# SoC_FPGA_67_68_69_DDR4.net
KiCad netlist of a schematic drawn in Altium Designer
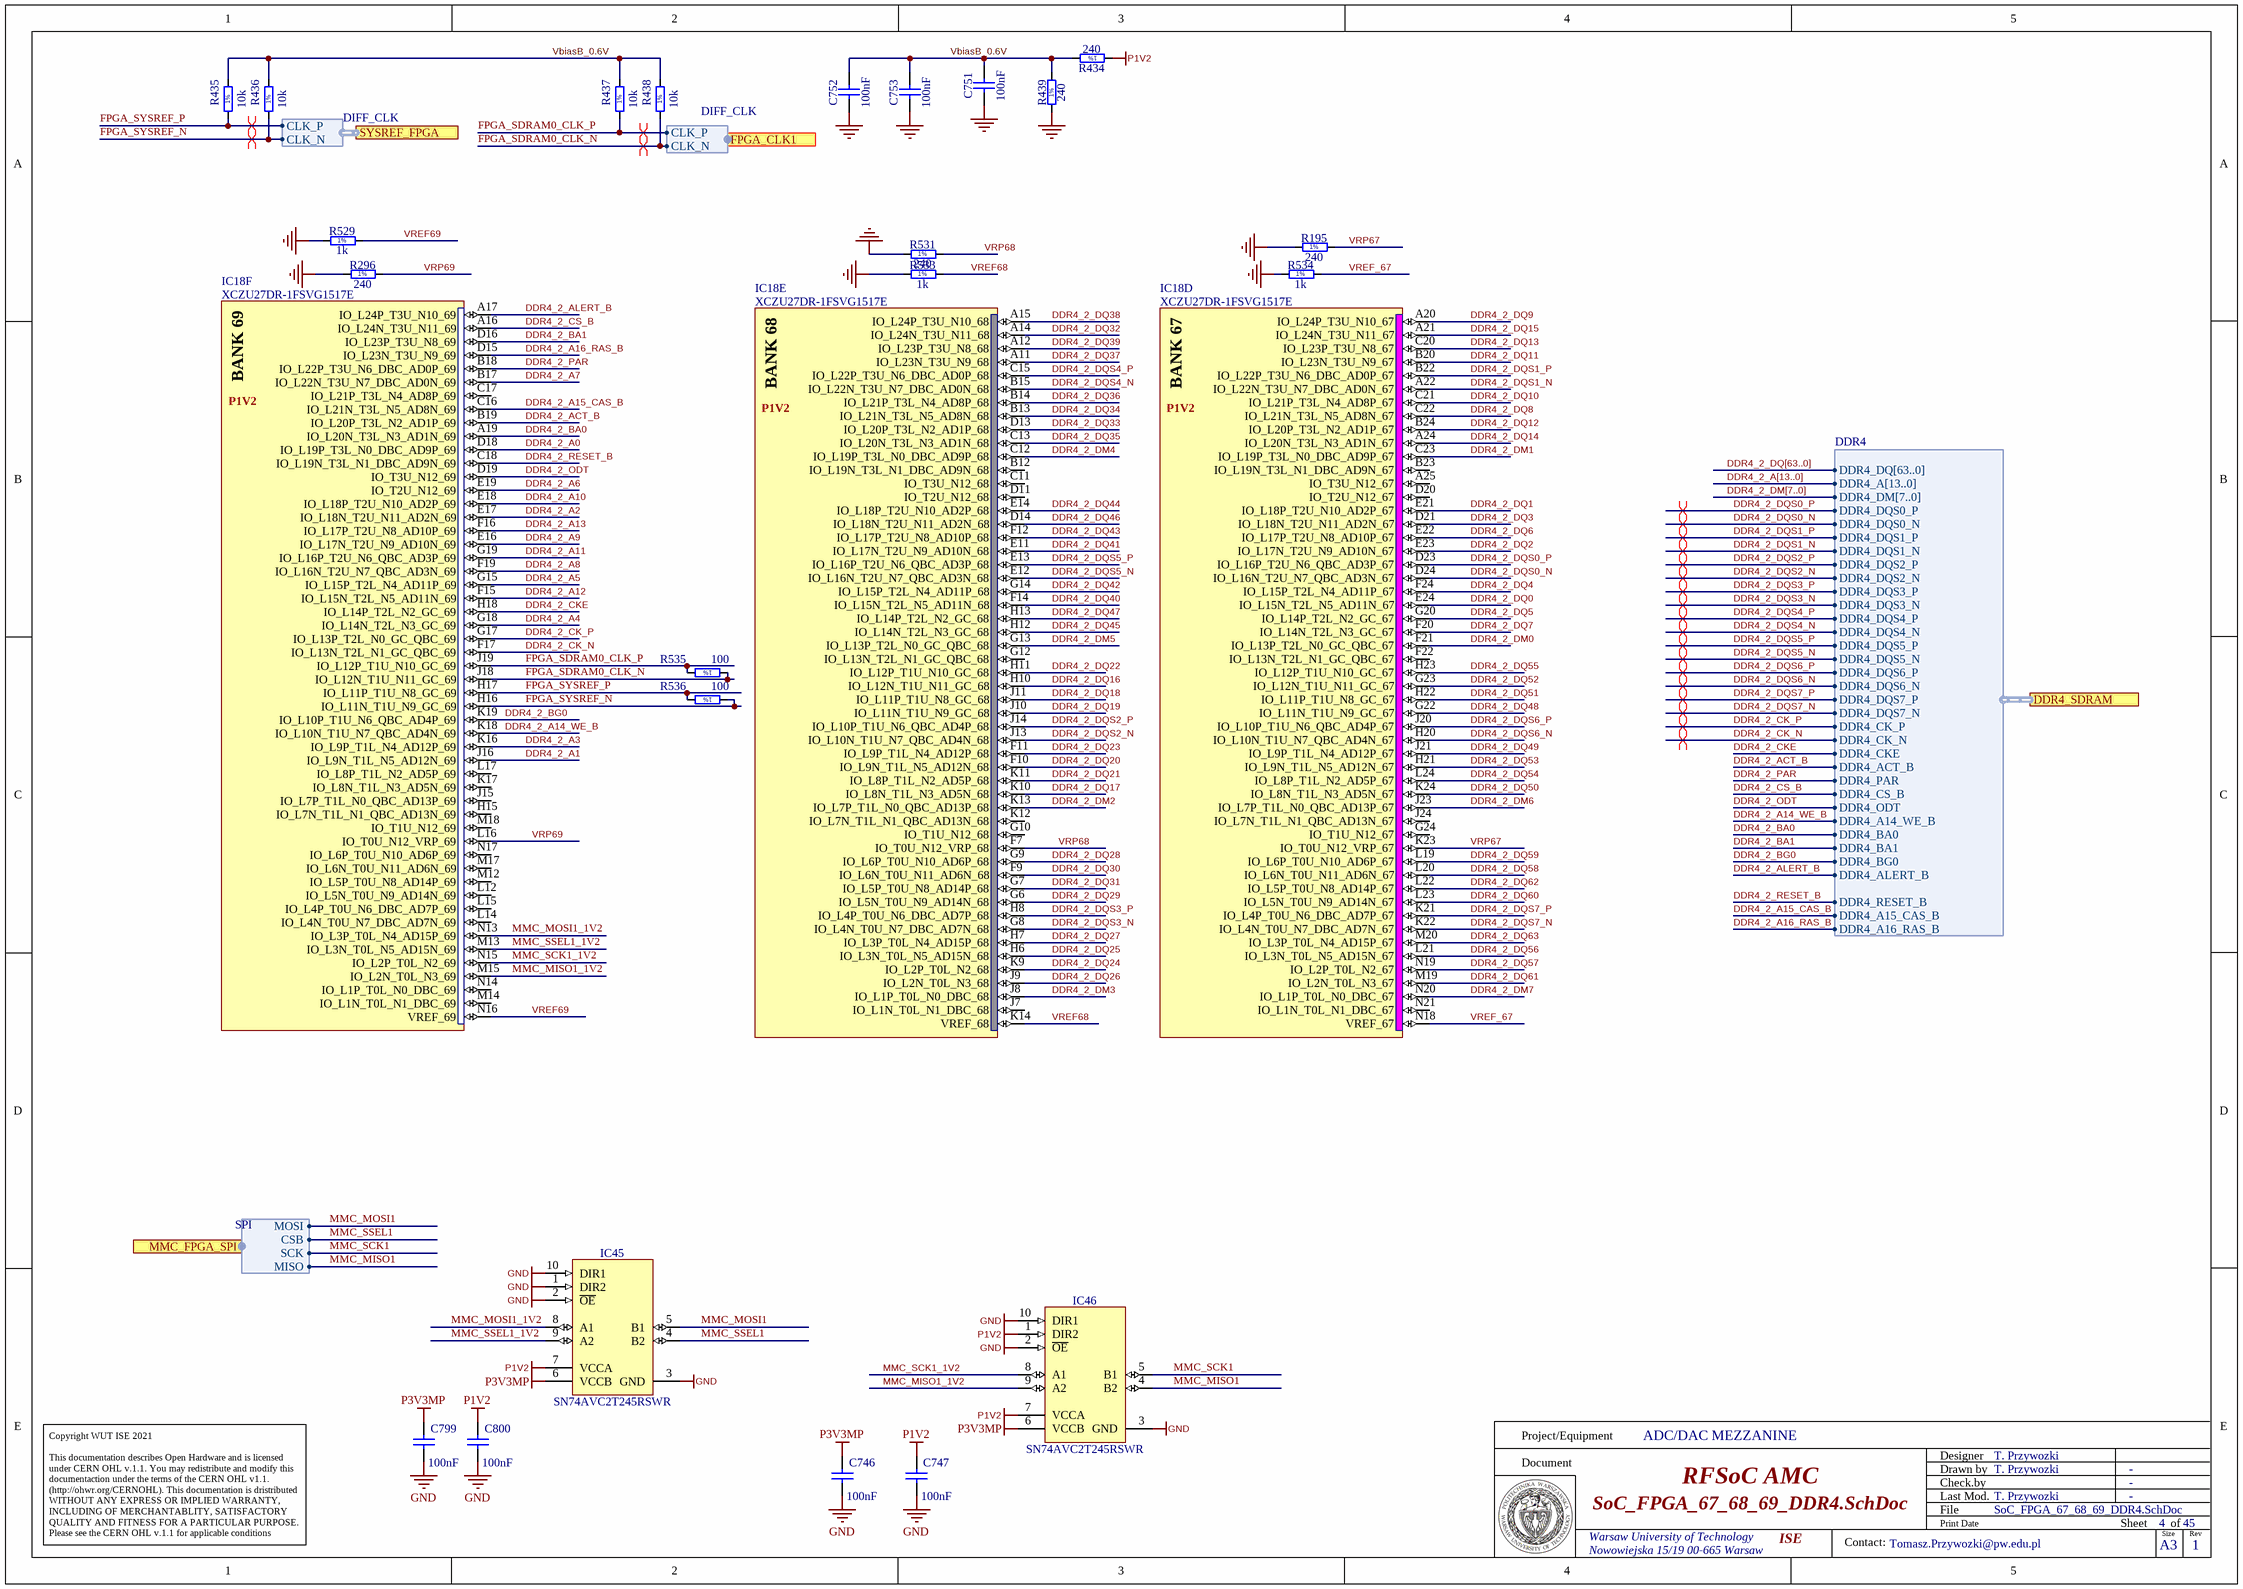
[diagram p0: SoC_FPGA_67_68_69_DDR4.SchDoc]

(export (version "E")
  (design (tool "Eeschema 10.0.6"))
  (components
    (comp (ref "C746")
      (value "100nF")
      (footprint "CAPC0603X33N")
      (description "Non-polarised capacitor")
      (fields
        (field (name "MANUFACTURER PART NUMBER") "CC0201_100NF_6.3V_10%_X5R")
        (field (name "MANUFACTURER") "GENERIC")
        (field (name "AUTHOR") "CERN DEM JLC")
      )
      (libsource (lib "Capacitors") (part "Capacitor - non polarized"))
    )
    (comp (ref "C747")
      (value "100nF")
      (footprint "CAPC0603X33N")
      (description "Non-polarised capacitor")
      (fields
        (field (name "MANUFACTURER PART NUMBER") "CC0201_100NF_6.3V_10%_X5R")
        (field (name "MANUFACTURER") "GENERIC")
        (field (name "AUTHOR") "CERN DEM JLC")
      )
      (libsource (lib "Capacitors") (part "Capacitor - non polarized"))
    )
    (comp (ref "C751")
      (value "100nF")
      (footprint "CAPC0603X33N")
      (description "Non-polarised capacitor")
      (fields
        (field (name "MANUFACTURER PART NUMBER") "CC0201_100NF_6.3V_10%_X5R")
        (field (name "MANUFACTURER") "GENERIC")
        (field (name "AUTHOR") "CERN DEM JLC")
      )
      (libsource (lib "Capacitors") (part "Capacitor - non polarized"))
    )
    (comp (ref "C752")
      (value "100nF")
      (footprint "CAPC0603X33N")
      (description "Non-polarised capacitor")
      (fields
        (field (name "MANUFACTURER PART NUMBER") "CC0201_100NF_6.3V_10%_X5R")
        (field (name "MANUFACTURER") "GENERIC")
        (field (name "AUTHOR") "CERN DEM JLC")
      )
      (libsource (lib "Capacitors") (part "Capacitor - non polarized"))
    )
    (comp (ref "C753")
      (value "100nF")
      (footprint "CAPC0603X33N")
      (description "Non-polarised capacitor")
      (fields
        (field (name "MANUFACTURER PART NUMBER") "CC0201_100NF_6.3V_10%_X5R")
        (field (name "MANUFACTURER") "GENERIC")
        (field (name "AUTHOR") "CERN DEM JLC")
      )
      (libsource (lib "Capacitors") (part "Capacitor - non polarized"))
    )
    (comp (ref "C799")
      (value "100nF")
      (footprint "CAPC0603X33N")
      (description "Non-polarised capacitor")
      (fields
        (field (name "MANUFACTURER PART NUMBER") "CC0201_100NF_6.3V_10%_X5R")
        (field (name "MANUFACTURER") "GENERIC")
        (field (name "AUTHOR") "CERN DEM JLC")
      )
      (libsource (lib "Capacitors") (part "Capacitor - non polarized"))
    )
    (comp (ref "C800")
      (value "100nF")
      (footprint "CAPC0603X33N")
      (description "Non-polarised capacitor")
      (fields
        (field (name "MANUFACTURER PART NUMBER") "CC0201_100NF_6.3V_10%_X5R")
        (field (name "MANUFACTURER") "GENERIC")
        (field (name "AUTHOR") "CERN DEM JLC")
      )
      (libsource (lib "Capacitors") (part "Capacitor - non polarized"))
    )
    (comp (ref "IC18")
      (value "XCZU27DR-1FSVG1517E")
      (footprint "XILINX_FSVG1517 (XCZU27DR)")
      (fields (field (name "MANUFACTURER") "XILINX") (field (name "AUTHOR") "CERN DEM MR"))
      (libsource (lib "ICs And Semiconductors") (part "XCZU27DR-1FSVG1517E"))
    )
    (comp (ref "IC45")
      (value "SN74AVC2T245RSWR")
      (footprint "QFN40P140X180X55-10N")
      (description "Dual-Bit Dual-Supply Bus Transceiver With Configurable Voltage Translation and 3-State Outputs")
      (fields (field (name "MANUFACTURER") "TEXAS INSTRUMENTS") (field (name "AUTHOR") "CERN DEM JLC"))
      (libsource (lib "ICs And Semiconductors") (part "742T245"))
    )
    (comp (ref "IC46")
      (value "SN74AVC2T245RSWR")
      (footprint "QFN40P140X180X55-10N")
      (description "Dual-Bit Dual-Supply Bus Transceiver With Configurable Voltage Translation and 3-State Outputs")
      (fields (field (name "MANUFACTURER") "TEXAS INSTRUMENTS") (field (name "AUTHOR") "CERN DEM JLC"))
      (libsource (lib "ICs And Semiconductors") (part "742T245"))
    )
    (comp (ref "R195")
      (value "240")
      (footprint "RESC1005X40N")
      (description "Resistor - 1%")
      (fields
        (field (name "MANUFACTURER PART NUMBER") "R0402_240R_1%_0.0625W_100PPM")
        (field (name "MANUFACTURER") "GENERIC")
        (field (name "AUTHOR") "CERN DEM JLC")
      )
      (libsource (lib "Resistors") (part "Resistor - 1%"))
    )
    (comp (ref "R296")
      (value "240")
      (footprint "RESC1005X40N")
      (description "Resistor - 1%")
      (fields
        (field (name "MANUFACTURER PART NUMBER") "R0402_240R_1%_0.0625W_100PPM")
        (field (name "MANUFACTURER") "GENERIC")
        (field (name "AUTHOR") "CERN DEM JLC")
      )
      (libsource (lib "Resistors") (part "Resistor - 1%"))
    )
    (comp (ref "R434")
      (value "240")
      (footprint "RESC1005X40N")
      (description "Resistor - 1%")
      (fields
        (field (name "MANUFACTURER PART NUMBER") "R0402_240R_1%_0.0625W_100PPM")
        (field (name "MANUFACTURER") "GENERIC")
        (field (name "AUTHOR") "CERN DEM JLC")
      )
      (libsource (lib "Resistors") (part "Resistor - 1%"))
    )
    (comp (ref "R435")
      (value "10k")
      (footprint "RESC1005X40N")
      (description "Resistor - 1%")
      (fields
        (field (name "MANUFACTURER PART NUMBER") "R0402_10K_1%_0.0625W_100PPM")
        (field (name "MANUFACTURER") "GENERIC")
        (field (name "AUTHOR") "CERN DEM JLC")
      )
      (libsource (lib "Resistors") (part "Resistor - 1%"))
    )
    (comp (ref "R436")
      (value "10k")
      (footprint "RESC1005X40N")
      (description "Resistor - 1%")
      (fields
        (field (name "MANUFACTURER PART NUMBER") "R0402_10K_1%_0.0625W_100PPM")
        (field (name "MANUFACTURER") "GENERIC")
        (field (name "AUTHOR") "CERN DEM JLC")
      )
      (libsource (lib "Resistors") (part "Resistor - 1%"))
    )
    (comp (ref "R437")
      (value "10k")
      (footprint "RESC1005X40N")
      (description "Resistor - 1%")
      (fields
        (field (name "MANUFACTURER PART NUMBER") "R0402_10K_1%_0.0625W_100PPM")
        (field (name "MANUFACTURER") "GENERIC")
        (field (name "AUTHOR") "CERN DEM JLC")
      )
      (libsource (lib "Resistors") (part "Resistor - 1%"))
    )
    (comp (ref "R438")
      (value "10k")
      (footprint "RESC1005X40N")
      (description "Resistor - 1%")
      (fields
        (field (name "MANUFACTURER PART NUMBER") "R0402_10K_1%_0.0625W_100PPM")
        (field (name "MANUFACTURER") "GENERIC")
        (field (name "AUTHOR") "CERN DEM JLC")
      )
      (libsource (lib "Resistors") (part "Resistor - 1%"))
    )
    (comp (ref "R439")
      (value "240")
      (footprint "RESC1005X40N")
      (description "Resistor - 1%")
      (fields
        (field (name "MANUFACTURER PART NUMBER") "R0402_240R_1%_0.0625W_100PPM")
        (field (name "MANUFACTURER") "GENERIC")
        (field (name "AUTHOR") "CERN DEM JLC")
      )
      (libsource (lib "Resistors") (part "Resistor - 1%"))
    )
    (comp (ref "R529")
      (value "1k")
      (footprint "RESC1005X40N")
      (description "Resistor - 1%")
      (fields
        (field (name "MANUFACTURER PART NUMBER") "R0402_1K_1%_0.0625W_100PPM")
        (field (name "MANUFACTURER") "GENERIC")
        (field (name "AUTHOR") "CERN DEM JLC")
      )
      (libsource (lib "Resistors") (part "Resistor - 1%"))
    )
    (comp (ref "R531")
      (value "240")
      (footprint "RESC1005X40N")
      (description "Resistor - 1%")
      (fields
        (field (name "MANUFACTURER PART NUMBER") "R0402_240R_1%_0.0625W_100PPM")
        (field (name "MANUFACTURER") "GENERIC")
        (field (name "AUTHOR") "CERN DEM JLC")
      )
      (libsource (lib "Resistors") (part "Resistor - 1%"))
    )
    (comp (ref "R533")
      (value "1k")
      (footprint "RESC1005X40N")
      (description "Resistor - 1%")
      (fields
        (field (name "MANUFACTURER PART NUMBER") "R0402_1K_1%_0.0625W_100PPM")
        (field (name "MANUFACTURER") "GENERIC")
        (field (name "AUTHOR") "CERN DEM JLC")
      )
      (libsource (lib "Resistors") (part "Resistor - 1%"))
    )
    (comp (ref "R534")
      (value "1k")
      (footprint "RESC1005X40N")
      (description "Resistor - 1%")
      (fields
        (field (name "MANUFACTURER PART NUMBER") "R0402_1K_1%_0.0625W_100PPM")
        (field (name "MANUFACTURER") "GENERIC")
        (field (name "AUTHOR") "CERN DEM JLC")
      )
      (libsource (lib "Resistors") (part "Resistor - 1%"))
    )
    (comp (ref "R535")
      (value "100")
      (footprint "RESC1005X40N")
      (description "Resistor - 1%")
      (fields
        (field (name "MANUFACTURER PART NUMBER") "R0402_100R_1%_0.0625W_100PPM")
        (field (name "MANUFACTURER") "GENERIC")
        (field (name "AUTHOR") "CERN DEM JLC")
      )
      (libsource (lib "Resistors") (part "Resistor - 1%"))
    )
    (comp (ref "R536")
      (value "100")
      (footprint "RESC1005X40N")
      (description "Resistor - 1%")
      (fields
        (field (name "MANUFACTURER PART NUMBER") "R0402_100R_1%_0.0625W_100PPM")
        (field (name "MANUFACTURER") "GENERIC")
        (field (name "AUTHOR") "CERN DEM JLC")
      )
      (libsource (lib "Resistors") (part "Resistor - 1%"))
    )
  )
  (nets
    (net (code "4") (name "/DDR4_2_A0") (class "Default")
      (node (ref "IC18") (pin "D18") (pinfunction "IO_L19P_T3L_N0_DBC_AD9P_69_D18") (pintype "bidirectional"))
    )
    (net (code "5") (name "/DDR4_2_A1") (class "Default")
      (node (ref "IC18") (pin "J16") (pinfunction "IO_L9N_T1L_N5_AD12N_69_J16") (pintype "bidirectional"))
    )
    (net (code "6") (name "/DDR4_2_A2") (class "Default")
      (node (ref "IC18") (pin "E17") (pinfunction "IO_L18N_T2U_N11_AD2N_69_E17") (pintype "bidirectional"))
    )
    (net (code "7") (name "/DDR4_2_A3") (class "Default")
      (node (ref "IC18") (pin "K16") (pinfunction "IO_L9P_T1L_N4_AD12P_69_K16") (pintype "bidirectional"))
    )
    (net (code "8") (name "/DDR4_2_A4") (class "Default")
      (node (ref "IC18") (pin "G18") (pinfunction "IO_L14N_T2L_N3_GC_69_G18") (pintype "bidirectional"))
    )
    (net (code "9") (name "/DDR4_2_A5") (class "Default")
      (node (ref "IC18") (pin "G15") (pinfunction "IO_L15P_T2L_N4_AD11P_69_G15") (pintype "bidirectional"))
    )
    (net (code "10") (name "/DDR4_2_A6") (class "Default")
      (node (ref "IC18") (pin "E19") (pinfunction "IO_T2U_N12_69_E19") (pintype "bidirectional"))
    )
    (net (code "11") (name "/DDR4_2_A7") (class "Default")
      (node (ref "IC18") (pin "B17") (pinfunction "IO_L22N_T3U_N7_DBC_AD0N_69_B17") (pintype "bidirectional"))
    )
    (net (code "12") (name "/DDR4_2_A8") (class "Default")
      (node (ref "IC18") (pin "F19") (pinfunction "IO_L16N_T2U_N7_QBC_AD3N_69_F19") (pintype "bidirectional"))
    )
    (net (code "13") (name "/DDR4_2_A9") (class "Default")
      (node (ref "IC18") (pin "E16") (pinfunction "IO_L17N_T2U_N9_AD10N_69_E16") (pintype "bidirectional"))
    )
    (net (code "14") (name "/DDR4_2_A10") (class "Default")
      (node (ref "IC18") (pin "E18") (pinfunction "IO_L18P_T2U_N10_AD2P_69_E18") (pintype "bidirectional"))
    )
    (net (code "15") (name "/DDR4_2_A11") (class "Default")
      (node (ref "IC18") (pin "G19") (pinfunction "IO_L16P_T2U_N6_QBC_AD3P_69_G19") (pintype "bidirectional"))
    )
    (net (code "16") (name "/DDR4_2_A12") (class "Default")
      (node (ref "IC18") (pin "F15") (pinfunction "IO_L15N_T2L_N5_AD11N_69_F15") (pintype "bidirectional"))
    )
    (net (code "17") (name "/DDR4_2_A13") (class "Default")
      (node (ref "IC18") (pin "F16") (pinfunction "IO_L17P_T2U_N8_AD10P_69_F16") (pintype "bidirectional"))
    )
    (net (code "18") (name "/DDR4_2_A14_WE_B") (class "Default")
      (node (ref "IC18") (pin "K18") (pinfunction "IO_L10N_T1U_N7_QBC_AD4N_69_K18") (pintype "bidirectional"))
    )
    (net (code "19") (name "/DDR4_2_A15_CAS_B") (class "Default")
      (node (ref "IC18") (pin "C16") (pinfunction "IO_L21N_T3L_N5_AD8N_69_C16") (pintype "bidirectional"))
    )
    (net (code "20") (name "/DDR4_2_A16_RAS_B") (class "Default")
      (node (ref "IC18") (pin "D15") (pinfunction "IO_L23N_T3U_N9_69_D15") (pintype "bidirectional"))
    )
    (net (code "21") (name "/DDR4_2_ACT_B") (class "Default")
      (node (ref "IC18") (pin "B19") (pinfunction "IO_L20P_T3L_N2_AD1P_69_B19") (pintype "bidirectional"))
    )
    (net (code "22") (name "/DDR4_2_ALERT_B") (class "Default")
      (node (ref "IC18") (pin "A17") (pinfunction "IO_L24P_T3U_N10_69_A17") (pintype "bidirectional"))
    )
    (net (code "24") (name "/DDR4_2_BA0") (class "Default")
      (node (ref "IC18") (pin "A19") (pinfunction "IO_L20N_T3L_N3_AD1N_69_A19") (pintype "bidirectional"))
    )
    (net (code "25") (name "/DDR4_2_BA1") (class "Default")
      (node (ref "IC18") (pin "D16") (pinfunction "IO_L23P_T3U_N8_69_D16") (pintype "bidirectional"))
    )
    (net (code "26") (name "/DDR4_2_BG0") (class "Default")
      (node (ref "IC18") (pin "K19") (pinfunction "IO_L10P_T1U_N6_QBC_AD4P_69_K19") (pintype "bidirectional"))
    )
    (net (code "27") (name "/DDR4_2_CKE") (class "Default")
      (node (ref "IC18") (pin "H18") (pinfunction "IO_L14P_T2L_N2_GC_69_H18") (pintype "bidirectional"))
    )
    (net (code "28") (name "/DDR4_2_CK_N") (class "Default")
      (node (ref "IC18") (pin "F17") (pinfunction "IO_L13N_T2L_N1_GC_QBC_69_F17") (pintype "bidirectional"))
    )
    (net (code "29") (name "/DDR4_2_CK_P") (class "Default")
      (node (ref "IC18") (pin "G17") (pinfunction "IO_L13P_T2L_N0_GC_QBC_69_G17") (pintype "bidirectional"))
    )
    (net (code "30") (name "/DDR4_2_CS_B") (class "Default")
      (node (ref "IC18") (pin "A16") (pinfunction "IO_L24N_T3U_N11_69_A16") (pintype "bidirectional"))
    )
    (net (code "31") (name "/DDR4_2_DM0") (class "Default")
      (node (ref "IC18") (pin "F21") (pinfunction "IO_L13P_T2L_N0_GC_QBC_67_F21") (pintype "bidirectional"))
    )
    (net (code "32") (name "/DDR4_2_DM1") (class "Default")
      (node (ref "IC18") (pin "C23") (pinfunction "IO_L19P_T3L_N0_DBC_AD9P_67_C23") (pintype "bidirectional"))
    )
    (net (code "33") (name "/DDR4_2_DM2") (class "Default")
      (node (ref "IC18") (pin "K13") (pinfunction "IO_L7P_T1L_N0_QBC_AD13P_68_K13") (pintype "bidirectional"))
    )
    (net (code "34") (name "/DDR4_2_DM3") (class "Default")
      (node (ref "IC18") (pin "J8") (pinfunction "IO_L1P_T0L_N0_DBC_68_J8") (pintype "bidirectional"))
    )
    (net (code "35") (name "/DDR4_2_DM4") (class "Default")
      (node (ref "IC18") (pin "C12") (pinfunction "IO_L19P_T3L_N0_DBC_AD9P_68_C12") (pintype "bidirectional"))
    )
    (net (code "36") (name "/DDR4_2_DM5") (class "Default")
      (node (ref "IC18") (pin "G13") (pinfunction "IO_L13P_T2L_N0_GC_QBC_68_G13") (pintype "bidirectional"))
    )
    (net (code "37") (name "/DDR4_2_DM6") (class "Default")
      (node (ref "IC18") (pin "J23") (pinfunction "IO_L7P_T1L_N0_QBC_AD13P_67_J23") (pintype "bidirectional"))
    )
    (net (code "38") (name "/DDR4_2_DM7") (class "Default")
      (node (ref "IC18") (pin "N20") (pinfunction "IO_L1P_T0L_N0_DBC_67_N20") (pintype "bidirectional"))
    )
    (net (code "40") (name "/DDR4_2_DQ0") (class "Default")
      (node (ref "IC18") (pin "E24") (pinfunction "IO_L15N_T2L_N5_AD11N_67_E24") (pintype "bidirectional"))
    )
    (net (code "41") (name "/DDR4_2_DQ1") (class "Default")
      (node (ref "IC18") (pin "E21") (pinfunction "IO_L18P_T2U_N10_AD2P_67_E21") (pintype "bidirectional"))
    )
    (net (code "42") (name "/DDR4_2_DQ2") (class "Default")
      (node (ref "IC18") (pin "E23") (pinfunction "IO_L17N_T2U_N9_AD10N_67_E23") (pintype "bidirectional"))
    )
    (net (code "43") (name "/DDR4_2_DQ3") (class "Default")
      (node (ref "IC18") (pin "D21") (pinfunction "IO_L18N_T2U_N11_AD2N_67_D21") (pintype "bidirectional"))
    )
    (net (code "44") (name "/DDR4_2_DQ4") (class "Default")
      (node (ref "IC18") (pin "F24") (pinfunction "IO_L15P_T2L_N4_AD11P_67_F24") (pintype "bidirectional"))
    )
    (net (code "45") (name "/DDR4_2_DQ5") (class "Default")
      (node (ref "IC18") (pin "G20") (pinfunction "IO_L14P_T2L_N2_GC_67_G20") (pintype "bidirectional"))
    )
    (net (code "46") (name "/DDR4_2_DQ6") (class "Default")
      (node (ref "IC18") (pin "E22") (pinfunction "IO_L17P_T2U_N8_AD10P_67_E22") (pintype "bidirectional"))
    )
    (net (code "47") (name "/DDR4_2_DQ7") (class "Default")
      (node (ref "IC18") (pin "F20") (pinfunction "IO_L14N_T2L_N3_GC_67_F20") (pintype "bidirectional"))
    )
    (net (code "48") (name "/DDR4_2_DQ8") (class "Default")
      (node (ref "IC18") (pin "C22") (pinfunction "IO_L21N_T3L_N5_AD8N_67_C22") (pintype "bidirectional"))
    )
    (net (code "49") (name "/DDR4_2_DQ9") (class "Default")
      (node (ref "IC18") (pin "A20") (pinfunction "IO_L24P_T3U_N10_67_A20") (pintype "bidirectional"))
    )
    (net (code "50") (name "/DDR4_2_DQ10") (class "Default")
      (node (ref "IC18") (pin "C21") (pinfunction "IO_L21P_T3L_N4_AD8P_67_C21") (pintype "bidirectional"))
    )
    (net (code "51") (name "/DDR4_2_DQ11") (class "Default")
      (node (ref "IC18") (pin "B20") (pinfunction "IO_L23N_T3U_N9_67_B20") (pintype "bidirectional"))
    )
    (net (code "52") (name "/DDR4_2_DQ12") (class "Default")
      (node (ref "IC18") (pin "B24") (pinfunction "IO_L20P_T3L_N2_AD1P_67_B24") (pintype "bidirectional"))
    )
    (net (code "53") (name "/DDR4_2_DQ13") (class "Default")
      (node (ref "IC18") (pin "C20") (pinfunction "IO_L23P_T3U_N8_67_C20") (pintype "bidirectional"))
    )
    (net (code "54") (name "/DDR4_2_DQ14") (class "Default")
      (node (ref "IC18") (pin "A24") (pinfunction "IO_L20N_T3L_N3_AD1N_67_A24") (pintype "bidirectional"))
    )
    (net (code "55") (name "/DDR4_2_DQ15") (class "Default")
      (node (ref "IC18") (pin "A21") (pinfunction "IO_L24N_T3U_N11_67_A21") (pintype "bidirectional"))
    )
    (net (code "56") (name "/DDR4_2_DQ16") (class "Default")
      (node (ref "IC18") (pin "H10") (pinfunction "IO_L12N_T1U_N11_GC_68_H10") (pintype "bidirectional"))
    )
    (net (code "57") (name "/DDR4_2_DQ17") (class "Default")
      (node (ref "IC18") (pin "K10") (pinfunction "IO_L8N_T1L_N3_AD5N_68_K10") (pintype "bidirectional"))
    )
    (net (code "58") (name "/DDR4_2_DQ18") (class "Default")
      (node (ref "IC18") (pin "J11") (pinfunction "IO_L11P_T1U_N8_GC_68_J11") (pintype "bidirectional"))
    )
    (net (code "59") (name "/DDR4_2_DQ19") (class "Default")
      (node (ref "IC18") (pin "J10") (pinfunction "IO_L11N_T1U_N9_GC_68_J10") (pintype "bidirectional"))
    )
    (net (code "60") (name "/DDR4_2_DQ20") (class "Default")
      (node (ref "IC18") (pin "F10") (pinfunction "IO_L9N_T1L_N5_AD12N_68_F10") (pintype "bidirectional"))
    )
    (net (code "61") (name "/DDR4_2_DQ21") (class "Default")
      (node (ref "IC18") (pin "K11") (pinfunction "IO_L8P_T1L_N2_AD5P_68_K11") (pintype "bidirectional"))
    )
    (net (code "62") (name "/DDR4_2_DQ22") (class "Default")
      (node (ref "IC18") (pin "H11") (pinfunction "IO_L12P_T1U_N10_GC_68_H11") (pintype "bidirectional"))
    )
    (net (code "63") (name "/DDR4_2_DQ23") (class "Default")
      (node (ref "IC18") (pin "F11") (pinfunction "IO_L9P_T1L_N4_AD12P_68_F11") (pintype "bidirectional"))
    )
    (net (code "64") (name "/DDR4_2_DQ24") (class "Default")
      (node (ref "IC18") (pin "K9") (pinfunction "IO_L2P_T0L_N2_68_K9") (pintype "bidirectional"))
    )
    (net (code "65") (name "/DDR4_2_DQ25") (class "Default")
      (node (ref "IC18") (pin "H6") (pinfunction "IO_L3N_T0L_N5_AD15N_68_H6") (pintype "bidirectional"))
    )
    (net (code "66") (name "/DDR4_2_DQ26") (class "Default")
      (node (ref "IC18") (pin "J9") (pinfunction "IO_L2N_T0L_N3_68_J9") (pintype "bidirectional"))
    )
    (net (code "67") (name "/DDR4_2_DQ27") (class "Default")
      (node (ref "IC18") (pin "H7") (pinfunction "IO_L3P_T0L_N4_AD15P_68_H7") (pintype "bidirectional"))
    )
    (net (code "68") (name "/DDR4_2_DQ28") (class "Default")
      (node (ref "IC18") (pin "G9") (pinfunction "IO_L6P_T0U_N10_AD6P_68_G9") (pintype "bidirectional"))
    )
    (net (code "69") (name "/DDR4_2_DQ29") (class "Default")
      (node (ref "IC18") (pin "G6") (pinfunction "IO_L5N_T0U_N9_AD14N_68_G6") (pintype "bidirectional"))
    )
    (net (code "70") (name "/DDR4_2_DQ30") (class "Default")
      (node (ref "IC18") (pin "F9") (pinfunction "IO_L6N_T0U_N11_AD6N_68_F9") (pintype "bidirectional"))
    )
    (net (code "71") (name "/DDR4_2_DQ31") (class "Default")
      (node (ref "IC18") (pin "G7") (pinfunction "IO_L5P_T0U_N8_AD14P_68_G7") (pintype "bidirectional"))
    )
    (net (code "72") (name "/DDR4_2_DQ32") (class "Default")
      (node (ref "IC18") (pin "A14") (pinfunction "IO_L24N_T3U_N11_68_A14") (pintype "bidirectional"))
    )
    (net (code "73") (name "/DDR4_2_DQ33") (class "Default")
      (node (ref "IC18") (pin "D13") (pinfunction "IO_L20P_T3L_N2_AD1P_68_D13") (pintype "bidirectional"))
    )
    (net (code "74") (name "/DDR4_2_DQ34") (class "Default")
      (node (ref "IC18") (pin "B13") (pinfunction "IO_L21N_T3L_N5_AD8N_68_B13") (pintype "bidirectional"))
    )
    (net (code "75") (name "/DDR4_2_DQ35") (class "Default")
      (node (ref "IC18") (pin "C13") (pinfunction "IO_L20N_T3L_N3_AD1N_68_C13") (pintype "bidirectional"))
    )
    (net (code "76") (name "/DDR4_2_DQ36") (class "Default")
      (node (ref "IC18") (pin "B14") (pinfunction "IO_L21P_T3L_N4_AD8P_68_B14") (pintype "bidirectional"))
    )
    (net (code "77") (name "/DDR4_2_DQ37") (class "Default")
      (node (ref "IC18") (pin "A11") (pinfunction "IO_L23N_T3U_N9_68_A11") (pintype "bidirectional"))
    )
    (net (code "78") (name "/DDR4_2_DQ38") (class "Default")
      (node (ref "IC18") (pin "A15") (pinfunction "IO_L24P_T3U_N10_68_A15") (pintype "bidirectional"))
    )
    (net (code "79") (name "/DDR4_2_DQ39") (class "Default")
      (node (ref "IC18") (pin "A12") (pinfunction "IO_L23P_T3U_N8_68_A12") (pintype "bidirectional"))
    )
    (net (code "80") (name "/DDR4_2_DQ40") (class "Default")
      (node (ref "IC18") (pin "F14") (pinfunction "IO_L15N_T2L_N5_AD11N_68_F14") (pintype "bidirectional"))
    )
    (net (code "81") (name "/DDR4_2_DQ41") (class "Default")
      (node (ref "IC18") (pin "E11") (pinfunction "IO_L17N_T2U_N9_AD10N_68_E11") (pintype "bidirectional"))
    )
    (net (code "82") (name "/DDR4_2_DQ42") (class "Default")
      (node (ref "IC18") (pin "G14") (pinfunction "IO_L15P_T2L_N4_AD11P_68_G14") (pintype "bidirectional"))
    )
    (net (code "83") (name "/DDR4_2_DQ43") (class "Default")
      (node (ref "IC18") (pin "F12") (pinfunction "IO_L17P_T2U_N8_AD10P_68_F12") (pintype "bidirectional"))
    )
    (net (code "84") (name "/DDR4_2_DQ44") (class "Default")
      (node (ref "IC18") (pin "E14") (pinfunction "IO_L18P_T2U_N10_AD2P_68_E14") (pintype "bidirectional"))
    )
    (net (code "85") (name "/DDR4_2_DQ45") (class "Default")
      (node (ref "IC18") (pin "H12") (pinfunction "IO_L14N_T2L_N3_GC_68_H12") (pintype "bidirectional"))
    )
    (net (code "86") (name "/DDR4_2_DQ46") (class "Default")
      (node (ref "IC18") (pin "D14") (pinfunction "IO_L18N_T2U_N11_AD2N_68_D14") (pintype "bidirectional"))
    )
    (net (code "87") (name "/DDR4_2_DQ47") (class "Default")
      (node (ref "IC18") (pin "H13") (pinfunction "IO_L14P_T2L_N2_GC_68_H13") (pintype "bidirectional"))
    )
    (net (code "88") (name "/DDR4_2_DQ48") (class "Default")
      (node (ref "IC18") (pin "G22") (pinfunction "IO_L11N_T1U_N9_GC_67_G22") (pintype "bidirectional"))
    )
    (net (code "89") (name "/DDR4_2_DQ49") (class "Default")
      (node (ref "IC18") (pin "J21") (pinfunction "IO_L9P_T1L_N4_AD12P_67_J21") (pintype "bidirectional"))
    )
    (net (code "90") (name "/DDR4_2_DQ50") (class "Default")
      (node (ref "IC18") (pin "K24") (pinfunction "IO_L8N_T1L_N3_AD5N_67_K24") (pintype "bidirectional"))
    )
    (net (code "91") (name "/DDR4_2_DQ51") (class "Default")
      (node (ref "IC18") (pin "H22") (pinfunction "IO_L11P_T1U_N8_GC_67_H22") (pintype "bidirectional"))
    )
    (net (code "92") (name "/DDR4_2_DQ52") (class "Default")
      (node (ref "IC18") (pin "G23") (pinfunction "IO_L12N_T1U_N11_GC_67_G23") (pintype "bidirectional"))
    )
    (net (code "93") (name "/DDR4_2_DQ53") (class "Default")
      (node (ref "IC18") (pin "H21") (pinfunction "IO_L9N_T1L_N5_AD12N_67_H21") (pintype "bidirectional"))
    )
    (net (code "94") (name "/DDR4_2_DQ54") (class "Default")
      (node (ref "IC18") (pin "L24") (pinfunction "IO_L8P_T1L_N2_AD5P_67_L24") (pintype "bidirectional"))
    )
    (net (code "95") (name "/DDR4_2_DQ55") (class "Default")
      (node (ref "IC18") (pin "H23") (pinfunction "IO_L12P_T1U_N10_GC_67_H23") (pintype "bidirectional"))
    )
    (net (code "96") (name "/DDR4_2_DQ56") (class "Default")
      (node (ref "IC18") (pin "L21") (pinfunction "IO_L3N_T0L_N5_AD15N_67_L21") (pintype "bidirectional"))
    )
    (net (code "97") (name "/DDR4_2_DQ57") (class "Default")
      (node (ref "IC18") (pin "N19") (pinfunction "IO_L2P_T0L_N2_67_N19") (pintype "bidirectional"))
    )
    (net (code "98") (name "/DDR4_2_DQ58") (class "Default")
      (node (ref "IC18") (pin "L20") (pinfunction "IO_L6N_T0U_N11_AD6N_67_L20") (pintype "bidirectional"))
    )
    (net (code "99") (name "/DDR4_2_DQ59") (class "Default")
      (node (ref "IC18") (pin "L19") (pinfunction "IO_L6P_T0U_N10_AD6P_67_L19") (pintype "bidirectional"))
    )
    (net (code "100") (name "/DDR4_2_DQ60") (class "Default")
      (node (ref "IC18") (pin "L23") (pinfunction "IO_L5N_T0U_N9_AD14N_67_L23") (pintype "bidirectional"))
    )
    (net (code "101") (name "/DDR4_2_DQ61") (class "Default")
      (node (ref "IC18") (pin "M19") (pinfunction "IO_L2N_T0L_N3_67_M19") (pintype "bidirectional"))
    )
    (net (code "102") (name "/DDR4_2_DQ62") (class "Default")
      (node (ref "IC18") (pin "L22") (pinfunction "IO_L5P_T0U_N8_AD14P_67_L22") (pintype "bidirectional"))
    )
    (net (code "103") (name "/DDR4_2_DQ63") (class "Default")
      (node (ref "IC18") (pin "M20") (pinfunction "IO_L3P_T0L_N4_AD15P_67_M20") (pintype "bidirectional"))
    )
    (net (code "104") (name "/DDR4_2_DQS0_N") (class "Default")
      (node (ref "IC18") (pin "D24") (pinfunction "IO_L16N_T2U_N7_QBC_AD3N_67_D24") (pintype "bidirectional"))
    )
    (net (code "105") (name "/DDR4_2_DQS0_P") (class "Default")
      (node (ref "IC18") (pin "D23") (pinfunction "IO_L16P_T2U_N6_QBC_AD3P_67_D23") (pintype "bidirectional"))
    )
    (net (code "106") (name "/DDR4_2_DQS1_N") (class "Default")
      (node (ref "IC18") (pin "A22") (pinfunction "IO_L22N_T3U_N7_DBC_AD0N_67_A22") (pintype "bidirectional"))
    )
    (net (code "107") (name "/DDR4_2_DQS1_P") (class "Default")
      (node (ref "IC18") (pin "B22") (pinfunction "IO_L22P_T3U_N6_DBC_AD0P_67_B22") (pintype "bidirectional"))
    )
    (net (code "108") (name "/DDR4_2_DQS2_N") (class "Default")
      (node (ref "IC18") (pin "J13") (pinfunction "IO_L10N_T1U_N7_QBC_AD4N_68_J13") (pintype "bidirectional"))
    )
    (net (code "109") (name "/DDR4_2_DQS2_P") (class "Default")
      (node (ref "IC18") (pin "J14") (pinfunction "IO_L10P_T1U_N6_QBC_AD4P_68_J14") (pintype "bidirectional"))
    )
    (net (code "110") (name "/DDR4_2_DQS3_N") (class "Default")
      (node (ref "IC18") (pin "G8") (pinfunction "IO_L4N_T0U_N7_DBC_AD7N_68_G8") (pintype "bidirectional"))
    )
    (net (code "111") (name "/DDR4_2_DQS3_P") (class "Default")
      (node (ref "IC18") (pin "H8") (pinfunction "IO_L4P_T0U_N6_DBC_AD7P_68_H8") (pintype "bidirectional"))
    )
    (net (code "112") (name "/DDR4_2_DQS4_N") (class "Default")
      (node (ref "IC18") (pin "B15") (pinfunction "IO_L22N_T3U_N7_DBC_AD0N_68_B15") (pintype "bidirectional"))
    )
    (net (code "113") (name "/DDR4_2_DQS4_P") (class "Default")
      (node (ref "IC18") (pin "C15") (pinfunction "IO_L22P_T3U_N6_DBC_AD0P_68_C15") (pintype "bidirectional"))
    )
    (net (code "114") (name "/DDR4_2_DQS5_N") (class "Default")
      (node (ref "IC18") (pin "E12") (pinfunction "IO_L16N_T2U_N7_QBC_AD3N_68_E12") (pintype "bidirectional"))
    )
    (net (code "115") (name "/DDR4_2_DQS5_P") (class "Default")
      (node (ref "IC18") (pin "E13") (pinfunction "IO_L16P_T2U_N6_QBC_AD3P_68_E13") (pintype "bidirectional"))
    )
    (net (code "116") (name "/DDR4_2_DQS6_N") (class "Default")
      (node (ref "IC18") (pin "H20") (pinfunction "IO_L10N_T1U_N7_QBC_AD4N_67_H20") (pintype "bidirectional"))
    )
    (net (code "117") (name "/DDR4_2_DQS6_P") (class "Default")
      (node (ref "IC18") (pin "J20") (pinfunction "IO_L10P_T1U_N6_QBC_AD4P_67_J20") (pintype "bidirectional"))
    )
    (net (code "118") (name "/DDR4_2_DQS7_N") (class "Default")
      (node (ref "IC18") (pin "K22") (pinfunction "IO_L4N_T0U_N7_DBC_AD7N_67_K22") (pintype "bidirectional"))
    )
    (net (code "119") (name "/DDR4_2_DQS7_P") (class "Default")
      (node (ref "IC18") (pin "K21") (pinfunction "IO_L4P_T0U_N6_DBC_AD7P_67_K21") (pintype "bidirectional"))
    )
    (net (code "120") (name "/DDR4_2_ODT") (class "Default")
      (node (ref "IC18") (pin "D19") (pinfunction "IO_T3U_N12_69_D19") (pintype "bidirectional"))
    )
    (net (code "121") (name "/DDR4_2_PAR") (class "Default")
      (node (ref "IC18") (pin "B18") (pinfunction "IO_L22P_T3U_N6_DBC_AD0P_69_B18") (pintype "bidirectional"))
    )
    (net (code "122") (name "/DDR4_2_RESET_B") (class "Default")
      (node (ref "IC18") (pin "C18") (pinfunction "IO_L19N_T3L_N1_DBC_AD9N_69_C18") (pintype "bidirectional"))
    )
    (net (code "124") (name "/FPGA_SDRAM0_CLK_N") (class "Default")
      (node (ref "IC18") (pin "J18") (pinfunction "IO_L12N_T1U_N11_GC_69_J18") (pintype "bidirectional"))
      (node (ref "R438") (pin "1") (pinfunction "1_1") (pintype "passive"))
      (node (ref "R535") (pin "2") (pinfunction "2_2") (pintype "passive"))
    )
    (net (code "125") (name "/FPGA_SDRAM0_CLK_P") (class "Default")
      (node (ref "IC18") (pin "J19") (pinfunction "IO_L12P_T1U_N10_GC_69_J19") (pintype "bidirectional"))
      (node (ref "R437") (pin "1") (pinfunction "1_1") (pintype "passive"))
      (node (ref "R535") (pin "1") (pinfunction "1_1") (pintype "passive"))
    )
    (net (code "126") (name "/FPGA_SYSREF_N") (class "Default")
      (node (ref "IC18") (pin "H16") (pinfunction "IO_L11N_T1U_N9_GC_69_H16") (pintype "bidirectional"))
      (node (ref "R436") (pin "1") (pinfunction "1_1") (pintype "passive"))
      (node (ref "R536") (pin "2") (pinfunction "2_2") (pintype "passive"))
    )
    (net (code "127") (name "/FPGA_SYSREF_P") (class "Default")
      (node (ref "IC18") (pin "H17") (pinfunction "IO_L11P_T1U_N8_GC_69_H17") (pintype "bidirectional"))
      (node (ref "R435") (pin "1") (pinfunction "1_1") (pintype "passive"))
      (node (ref "R536") (pin "1") (pinfunction "1_1") (pintype "passive"))
    )
    (net (code "128") (name "/MMC_MISO1") (class "Default")
      (node (ref "IC46") (pin "4") (pinfunction "B2_4") (pintype "bidirectional"))
    )
    (net (code "129") (name "/MMC_MISO1_1V2") (class "Default")
      (node (ref "IC18") (pin "M15") (pinfunction "IO_L2N_T0L_N3_69_M15") (pintype "bidirectional"))
      (node (ref "IC46") (pin "9") (pinfunction "A2_9") (pintype "bidirectional"))
    )
    (net (code "130") (name "/MMC_MOSI1") (class "Default")
      (node (ref "IC45") (pin "5") (pinfunction "B1_5") (pintype "bidirectional"))
    )
    (net (code "131") (name "/MMC_MOSI1_1V2") (class "Default")
      (node (ref "IC18") (pin "N13") (pinfunction "IO_L3P_T0L_N4_AD15P_69_N13") (pintype "bidirectional"))
      (node (ref "IC45") (pin "8") (pinfunction "A1_8") (pintype "bidirectional"))
    )
    (net (code "132") (name "/MMC_SCK1") (class "Default")
      (node (ref "IC46") (pin "5") (pinfunction "B1_5") (pintype "bidirectional"))
    )
    (net (code "133") (name "/MMC_SCK1_1V2") (class "Default")
      (node (ref "IC18") (pin "N15") (pinfunction "IO_L2P_T0L_N2_69_N15") (pintype "bidirectional"))
      (node (ref "IC46") (pin "8") (pinfunction "A1_8") (pintype "bidirectional"))
    )
    (net (code "134") (name "/MMC_SSEL1") (class "Default")
      (node (ref "IC45") (pin "4") (pinfunction "B2_4") (pintype "bidirectional"))
    )
    (net (code "135") (name "/MMC_SSEL1_1V2") (class "Default")
      (node (ref "IC18") (pin "M13") (pinfunction "IO_L3N_T0L_N5_AD15N_69_M13") (pintype "bidirectional"))
      (node (ref "IC45") (pin "9") (pinfunction "A2_9") (pintype "bidirectional"))
    )
    (net (code "136") (name "/VREF68") (class "Default")
      (node (ref "IC18") (pin "K14") (pinfunction "VREF_68_K14") (pintype "bidirectional"))
      (node (ref "R533") (pin "2") (pinfunction "2_2") (pintype "passive"))
    )
    (net (code "137") (name "/VREF69") (class "Default")
      (node (ref "IC18") (pin "N16") (pinfunction "VREF_69_N16") (pintype "bidirectional"))
      (node (ref "R529") (pin "2") (pinfunction "2_2") (pintype "passive"))
    )
    (net (code "138") (name "/VREF_67") (class "Default")
      (node (ref "IC18") (pin "N18") (pinfunction "VREF_67_N18") (pintype "bidirectional"))
      (node (ref "R534") (pin "2") (pinfunction "2_2") (pintype "passive"))
    )
    (net (code "139") (name "/VRP67") (class "Default")
      (node (ref "IC18") (pin "K23") (pinfunction "IO_T0U_N12_VRP_67_K23") (pintype "bidirectional"))
      (node (ref "R195") (pin "2") (pinfunction "2_2") (pintype "passive"))
    )
    (net (code "140") (name "/VRP68") (class "Default")
      (node (ref "IC18") (pin "F7") (pinfunction "IO_T0U_N12_VRP_68_F7") (pintype "bidirectional"))
      (node (ref "R531") (pin "2") (pinfunction "2_2") (pintype "passive"))
    )
    (net (code "141") (name "/VRP69") (class "Default")
      (node (ref "IC18") (pin "L16") (pinfunction "IO_T0U_N12_VRP_69_L16") (pintype "bidirectional"))
      (node (ref "R296") (pin "2") (pinfunction "2_2") (pintype "passive"))
    )
    (net (code "142") (name "/VbiasB_0.6V") (class "Default")
      (node (ref "C751") (pin "1") (pinfunction "1_1") (pintype "passive"))
      (node (ref "C752") (pin "1") (pinfunction "1_1") (pintype "passive"))
      (node (ref "C753") (pin "1") (pinfunction "1_1") (pintype "passive"))
      (node (ref "R434") (pin "2") (pinfunction "2_2") (pintype "passive"))
      (node (ref "R435") (pin "2") (pinfunction "2_2") (pintype "passive"))
      (node (ref "R436") (pin "2") (pinfunction "2_2") (pintype "passive"))
      (node (ref "R437") (pin "2") (pinfunction "2_2") (pintype "passive"))
      (node (ref "R438") (pin "2") (pinfunction "2_2") (pintype "passive"))
      (node (ref "R439") (pin "2") (pinfunction "2_2") (pintype "passive"))
    )
    (net (code "146") (name "GND") (class "Default")
      (node (ref "C746") (pin "1") (pinfunction "1_1") (pintype "passive"))
      (node (ref "C747") (pin "1") (pinfunction "1_1") (pintype "passive"))
      (node (ref "C751") (pin "2") (pinfunction "2_2") (pintype "passive"))
      (node (ref "C752") (pin "2") (pinfunction "2_2") (pintype "passive"))
      (node (ref "C753") (pin "2") (pinfunction "2_2") (pintype "passive"))
      (node (ref "C799") (pin "1") (pinfunction "1_1") (pintype "passive"))
      (node (ref "C800") (pin "1") (pinfunction "1_1") (pintype "passive"))
      (node (ref "IC45") (pin "1") (pinfunction "DIR2_1") (pintype "input"))
      (node (ref "IC45") (pin "10") (pinfunction "DIR1_10") (pintype "input"))
      (node (ref "IC45") (pin "2") (pinfunction "~{OE}_2") (pintype "input"))
      (node (ref "IC45") (pin "3") (pinfunction "GND_3") (pintype "power_in"))
      (node (ref "IC46") (pin "10") (pinfunction "DIR1_10") (pintype "input"))
      (node (ref "IC46") (pin "2") (pinfunction "~{OE}_2") (pintype "input"))
      (node (ref "IC46") (pin "3") (pinfunction "GND_3") (pintype "power_in"))
      (node (ref "R195") (pin "1") (pinfunction "1_1") (pintype "passive"))
      (node (ref "R296") (pin "1") (pinfunction "1_1") (pintype "passive"))
      (node (ref "R439") (pin "1") (pinfunction "1_1") (pintype "passive"))
      (node (ref "R529") (pin "1") (pinfunction "1_1") (pintype "passive"))
      (node (ref "R531") (pin "1") (pinfunction "1_1") (pintype "passive"))
      (node (ref "R533") (pin "1") (pinfunction "1_1") (pintype "passive"))
      (node (ref "R534") (pin "1") (pinfunction "1_1") (pintype "passive"))
    )
    (net (code "147") (name "P1V2") (class "Default")
      (node (ref "C747") (pin "2") (pinfunction "2_2") (pintype "passive"))
      (node (ref "C800") (pin "2") (pinfunction "2_2") (pintype "passive"))
      (node (ref "IC45") (pin "7") (pinfunction "VCCA_7") (pintype "power_in"))
      (node (ref "IC46") (pin "1") (pinfunction "DIR2_1") (pintype "input"))
      (node (ref "IC46") (pin "7") (pinfunction "VCCA_7") (pintype "power_in"))
      (node (ref "R434") (pin "1") (pinfunction "1_1") (pintype "passive"))
    )
    (net (code "148") (name "P3V3MP") (class "Default")
      (node (ref "C746") (pin "2") (pinfunction "2_2") (pintype "passive"))
      (node (ref "C799") (pin "2") (pinfunction "2_2") (pintype "passive"))
      (node (ref "IC45") (pin "6") (pinfunction "VCCB_6") (pintype "power_in"))
      (node (ref "IC46") (pin "6") (pinfunction "VCCB_6") (pintype "power_in"))
    )
    (net (code "149") (name "unconnected-(IC18D-IO_L1N_T0L_N1_DBC_67-PadN21)") (class "Default")
      (node (ref "IC18") (pin "N21") (pinfunction "IO_L1N_T0L_N1_DBC_67_N21") (pintype "bidirectional"))
    )
    (net (code "150") (name "unconnected-(IC18D-IO_L7N_T1L_N1_QBC_AD13N_67-PadJ24)") (class "Default")
      (node (ref "IC18") (pin "J24") (pinfunction "IO_L7N_T1L_N1_QBC_AD13N_67_J24") (pintype "bidirectional"))
    )
    (net (code "151") (name "unconnected-(IC18D-IO_L13N_T2L_N1_GC_QBC_67-PadF22)") (class "Default")
      (node (ref "IC18") (pin "F22") (pinfunction "IO_L13N_T2L_N1_GC_QBC_67_F22") (pintype "bidirectional"))
    )
    (net (code "152") (name "unconnected-(IC18D-IO_L19N_T3L_N1_DBC_AD9N_67-PadB23)") (class "Default")
      (node (ref "IC18") (pin "B23") (pinfunction "IO_L19N_T3L_N1_DBC_AD9N_67_B23") (pintype "bidirectional"))
    )
    (net (code "153") (name "unconnected-(IC18D-IO_T1U_N12_67-PadG24)") (class "Default")
      (node (ref "IC18") (pin "G24") (pinfunction "IO_T1U_N12_67_G24") (pintype "bidirectional"))
    )
    (net (code "154") (name "unconnected-(IC18D-IO_T2U_N12_67-PadD20)") (class "Default")
      (node (ref "IC18") (pin "D20") (pinfunction "IO_T2U_N12_67_D20") (pintype "bidirectional"))
    )
    (net (code "155") (name "unconnected-(IC18D-IO_T3U_N12_67-PadA25)") (class "Default")
      (node (ref "IC18") (pin "A25") (pinfunction "IO_T3U_N12_67_A25") (pintype "bidirectional"))
    )
    (net (code "156") (name "unconnected-(IC18E-IO_L1N_T0L_N1_DBC_68-PadJ7)") (class "Default")
      (node (ref "IC18") (pin "J7") (pinfunction "IO_L1N_T0L_N1_DBC_68_J7") (pintype "bidirectional"))
    )
    (net (code "157") (name "unconnected-(IC18E-IO_L7N_T1L_N1_QBC_AD13N_68-PadK12)") (class "Default")
      (node (ref "IC18") (pin "K12") (pinfunction "IO_L7N_T1L_N1_QBC_AD13N_68_K12") (pintype "bidirectional"))
    )
    (net (code "158") (name "unconnected-(IC18E-IO_L13N_T2L_N1_GC_QBC_68-PadG12)") (class "Default")
      (node (ref "IC18") (pin "G12") (pinfunction "IO_L13N_T2L_N1_GC_QBC_68_G12") (pintype "bidirectional"))
    )
    (net (code "159") (name "unconnected-(IC18E-IO_L19N_T3L_N1_DBC_AD9N_68-PadB12)") (class "Default")
      (node (ref "IC18") (pin "B12") (pinfunction "IO_L19N_T3L_N1_DBC_AD9N_68_B12") (pintype "bidirectional"))
    )
    (net (code "160") (name "unconnected-(IC18E-IO_T1U_N12_68-PadG10)") (class "Default")
      (node (ref "IC18") (pin "G10") (pinfunction "IO_T1U_N12_68_G10") (pintype "bidirectional"))
    )
    (net (code "161") (name "unconnected-(IC18E-IO_T2U_N12_68-PadD11)") (class "Default")
      (node (ref "IC18") (pin "D11") (pinfunction "IO_T2U_N12_68_D11") (pintype "bidirectional"))
    )
    (net (code "162") (name "unconnected-(IC18E-IO_T3U_N12_68-PadC11)") (class "Default")
      (node (ref "IC18") (pin "C11") (pinfunction "IO_T3U_N12_68_C11") (pintype "bidirectional"))
    )
    (net (code "163") (name "unconnected-(IC18F-IO_L1N_T0L_N1_DBC_69-PadM14)") (class "Default")
      (node (ref "IC18") (pin "M14") (pinfunction "IO_L1N_T0L_N1_DBC_69_M14") (pintype "bidirectional"))
    )
    (net (code "164") (name "unconnected-(IC18F-IO_L1P_T0L_N0_DBC_69-PadN14)") (class "Default")
      (node (ref "IC18") (pin "N14") (pinfunction "IO_L1P_T0L_N0_DBC_69_N14") (pintype "bidirectional"))
    )
    (net (code "165") (name "unconnected-(IC18F-IO_L4N_T0U_N7_DBC_AD7N_69-PadL14)") (class "Default")
      (node (ref "IC18") (pin "L14") (pinfunction "IO_L4N_T0U_N7_DBC_AD7N_69_L14") (pintype "bidirectional"))
    )
    (net (code "166") (name "unconnected-(IC18F-IO_L4P_T0U_N6_DBC_AD7P_69-PadL15)") (class "Default")
      (node (ref "IC18") (pin "L15") (pinfunction "IO_L4P_T0U_N6_DBC_AD7P_69_L15") (pintype "bidirectional"))
    )
    (net (code "167") (name "unconnected-(IC18F-IO_L5N_T0U_N9_AD14N_69-PadL12)") (class "Default")
      (node (ref "IC18") (pin "L12") (pinfunction "IO_L5N_T0U_N9_AD14N_69_L12") (pintype "bidirectional"))
    )
    (net (code "168") (name "unconnected-(IC18F-IO_L5P_T0U_N8_AD14P_69-PadM12)") (class "Default")
      (node (ref "IC18") (pin "M12") (pinfunction "IO_L5P_T0U_N8_AD14P_69_M12") (pintype "bidirectional"))
    )
    (net (code "169") (name "unconnected-(IC18F-IO_L6N_T0U_N11_AD6N_69-PadM17)") (class "Default")
      (node (ref "IC18") (pin "M17") (pinfunction "IO_L6N_T0U_N11_AD6N_69_M17") (pintype "bidirectional"))
    )
    (net (code "170") (name "unconnected-(IC18F-IO_L6P_T0U_N10_AD6P_69-PadN17)") (class "Default")
      (node (ref "IC18") (pin "N17") (pinfunction "IO_L6P_T0U_N10_AD6P_69_N17") (pintype "bidirectional"))
    )
    (net (code "171") (name "unconnected-(IC18F-IO_L7N_T1L_N1_QBC_AD13N_69-PadH15)") (class "Default")
      (node (ref "IC18") (pin "H15") (pinfunction "IO_L7N_T1L_N1_QBC_AD13N_69_H15") (pintype "bidirectional"))
    )
    (net (code "172") (name "unconnected-(IC18F-IO_L7P_T1L_N0_QBC_AD13P_69-PadJ15)") (class "Default")
      (node (ref "IC18") (pin "J15") (pinfunction "IO_L7P_T1L_N0_QBC_AD13P_69_J15") (pintype "bidirectional"))
    )
    (net (code "173") (name "unconnected-(IC18F-IO_L8N_T1L_N3_AD5N_69-PadK17)") (class "Default")
      (node (ref "IC18") (pin "K17") (pinfunction "IO_L8N_T1L_N3_AD5N_69_K17") (pintype "bidirectional"))
    )
    (net (code "174") (name "unconnected-(IC18F-IO_L8P_T1L_N2_AD5P_69-PadL17)") (class "Default")
      (node (ref "IC18") (pin "L17") (pinfunction "IO_L8P_T1L_N2_AD5P_69_L17") (pintype "bidirectional"))
    )
    (net (code "175") (name "unconnected-(IC18F-IO_L21P_T3L_N4_AD8P_69-PadC17)") (class "Default")
      (node (ref "IC18") (pin "C17") (pinfunction "IO_L21P_T3L_N4_AD8P_69_C17") (pintype "bidirectional"))
    )
    (net (code "176") (name "unconnected-(IC18F-IO_T1U_N12_69-PadM18)") (class "Default")
      (node (ref "IC18") (pin "M18") (pinfunction "IO_T1U_N12_69_M18") (pintype "bidirectional"))
    )
  )
)
